# IR_LED_stick.net
KiCad netlist of a schematic drawn in EasyEDA
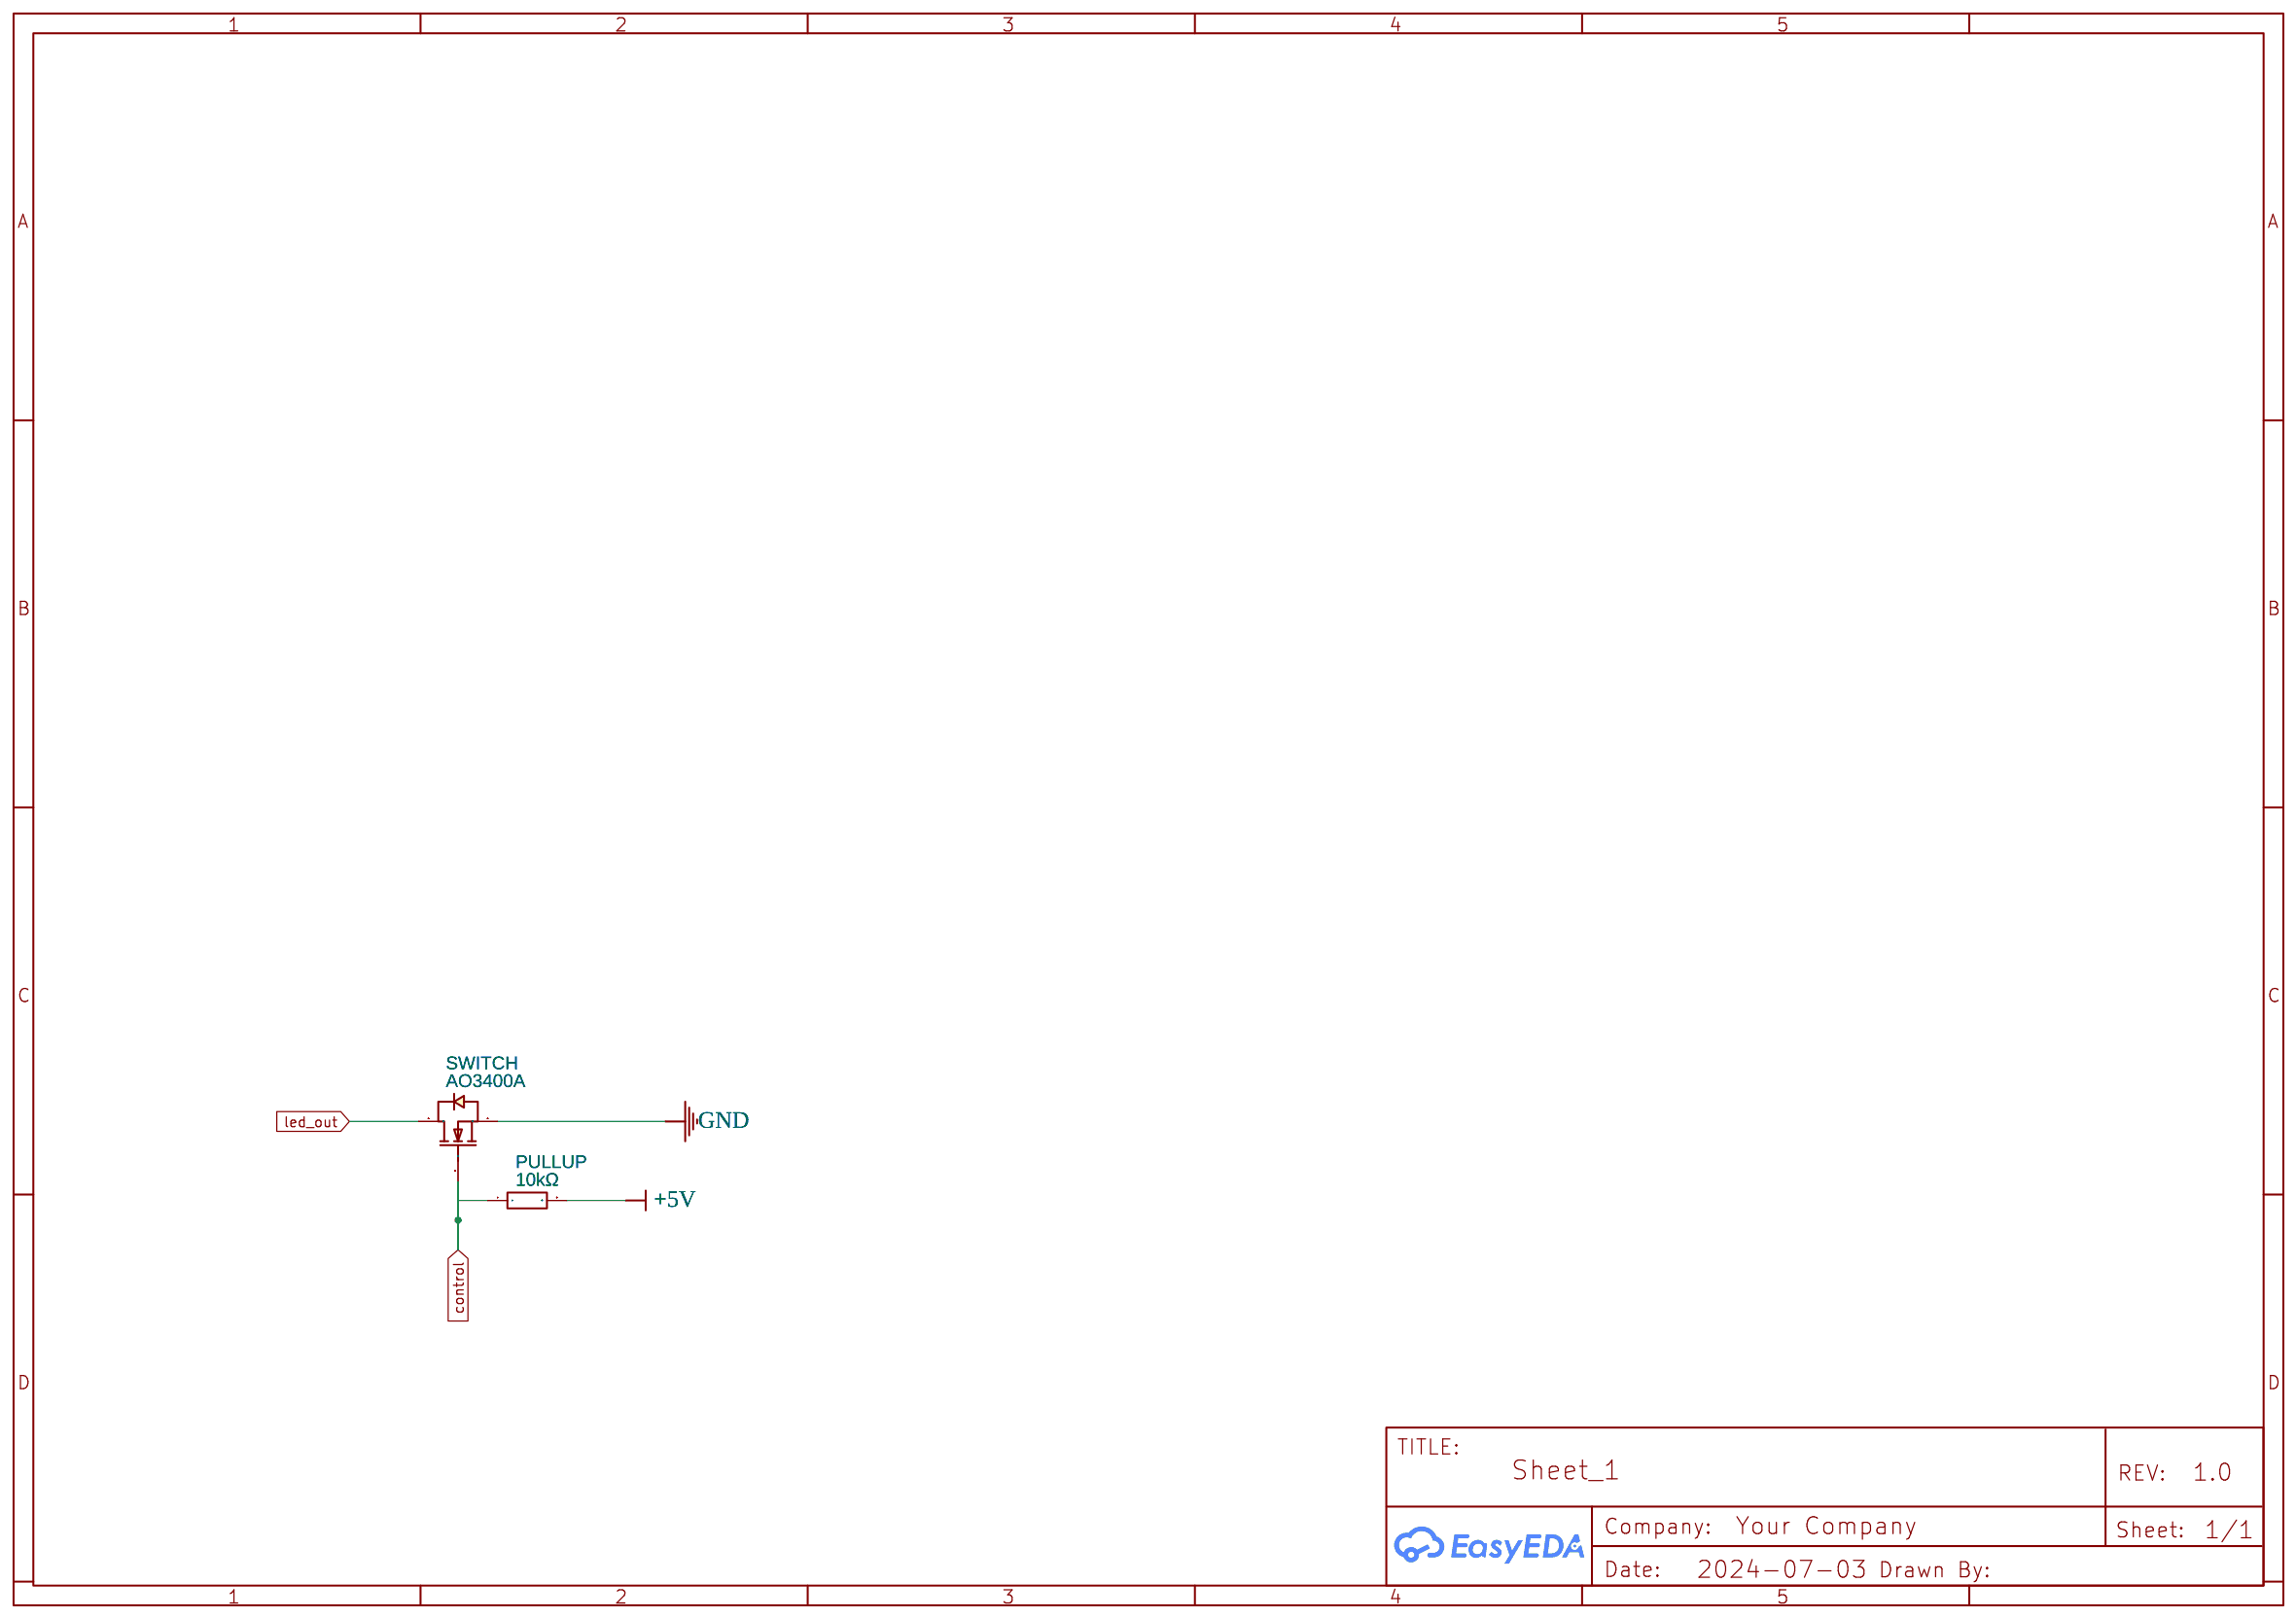
[diagram p0: Switch]
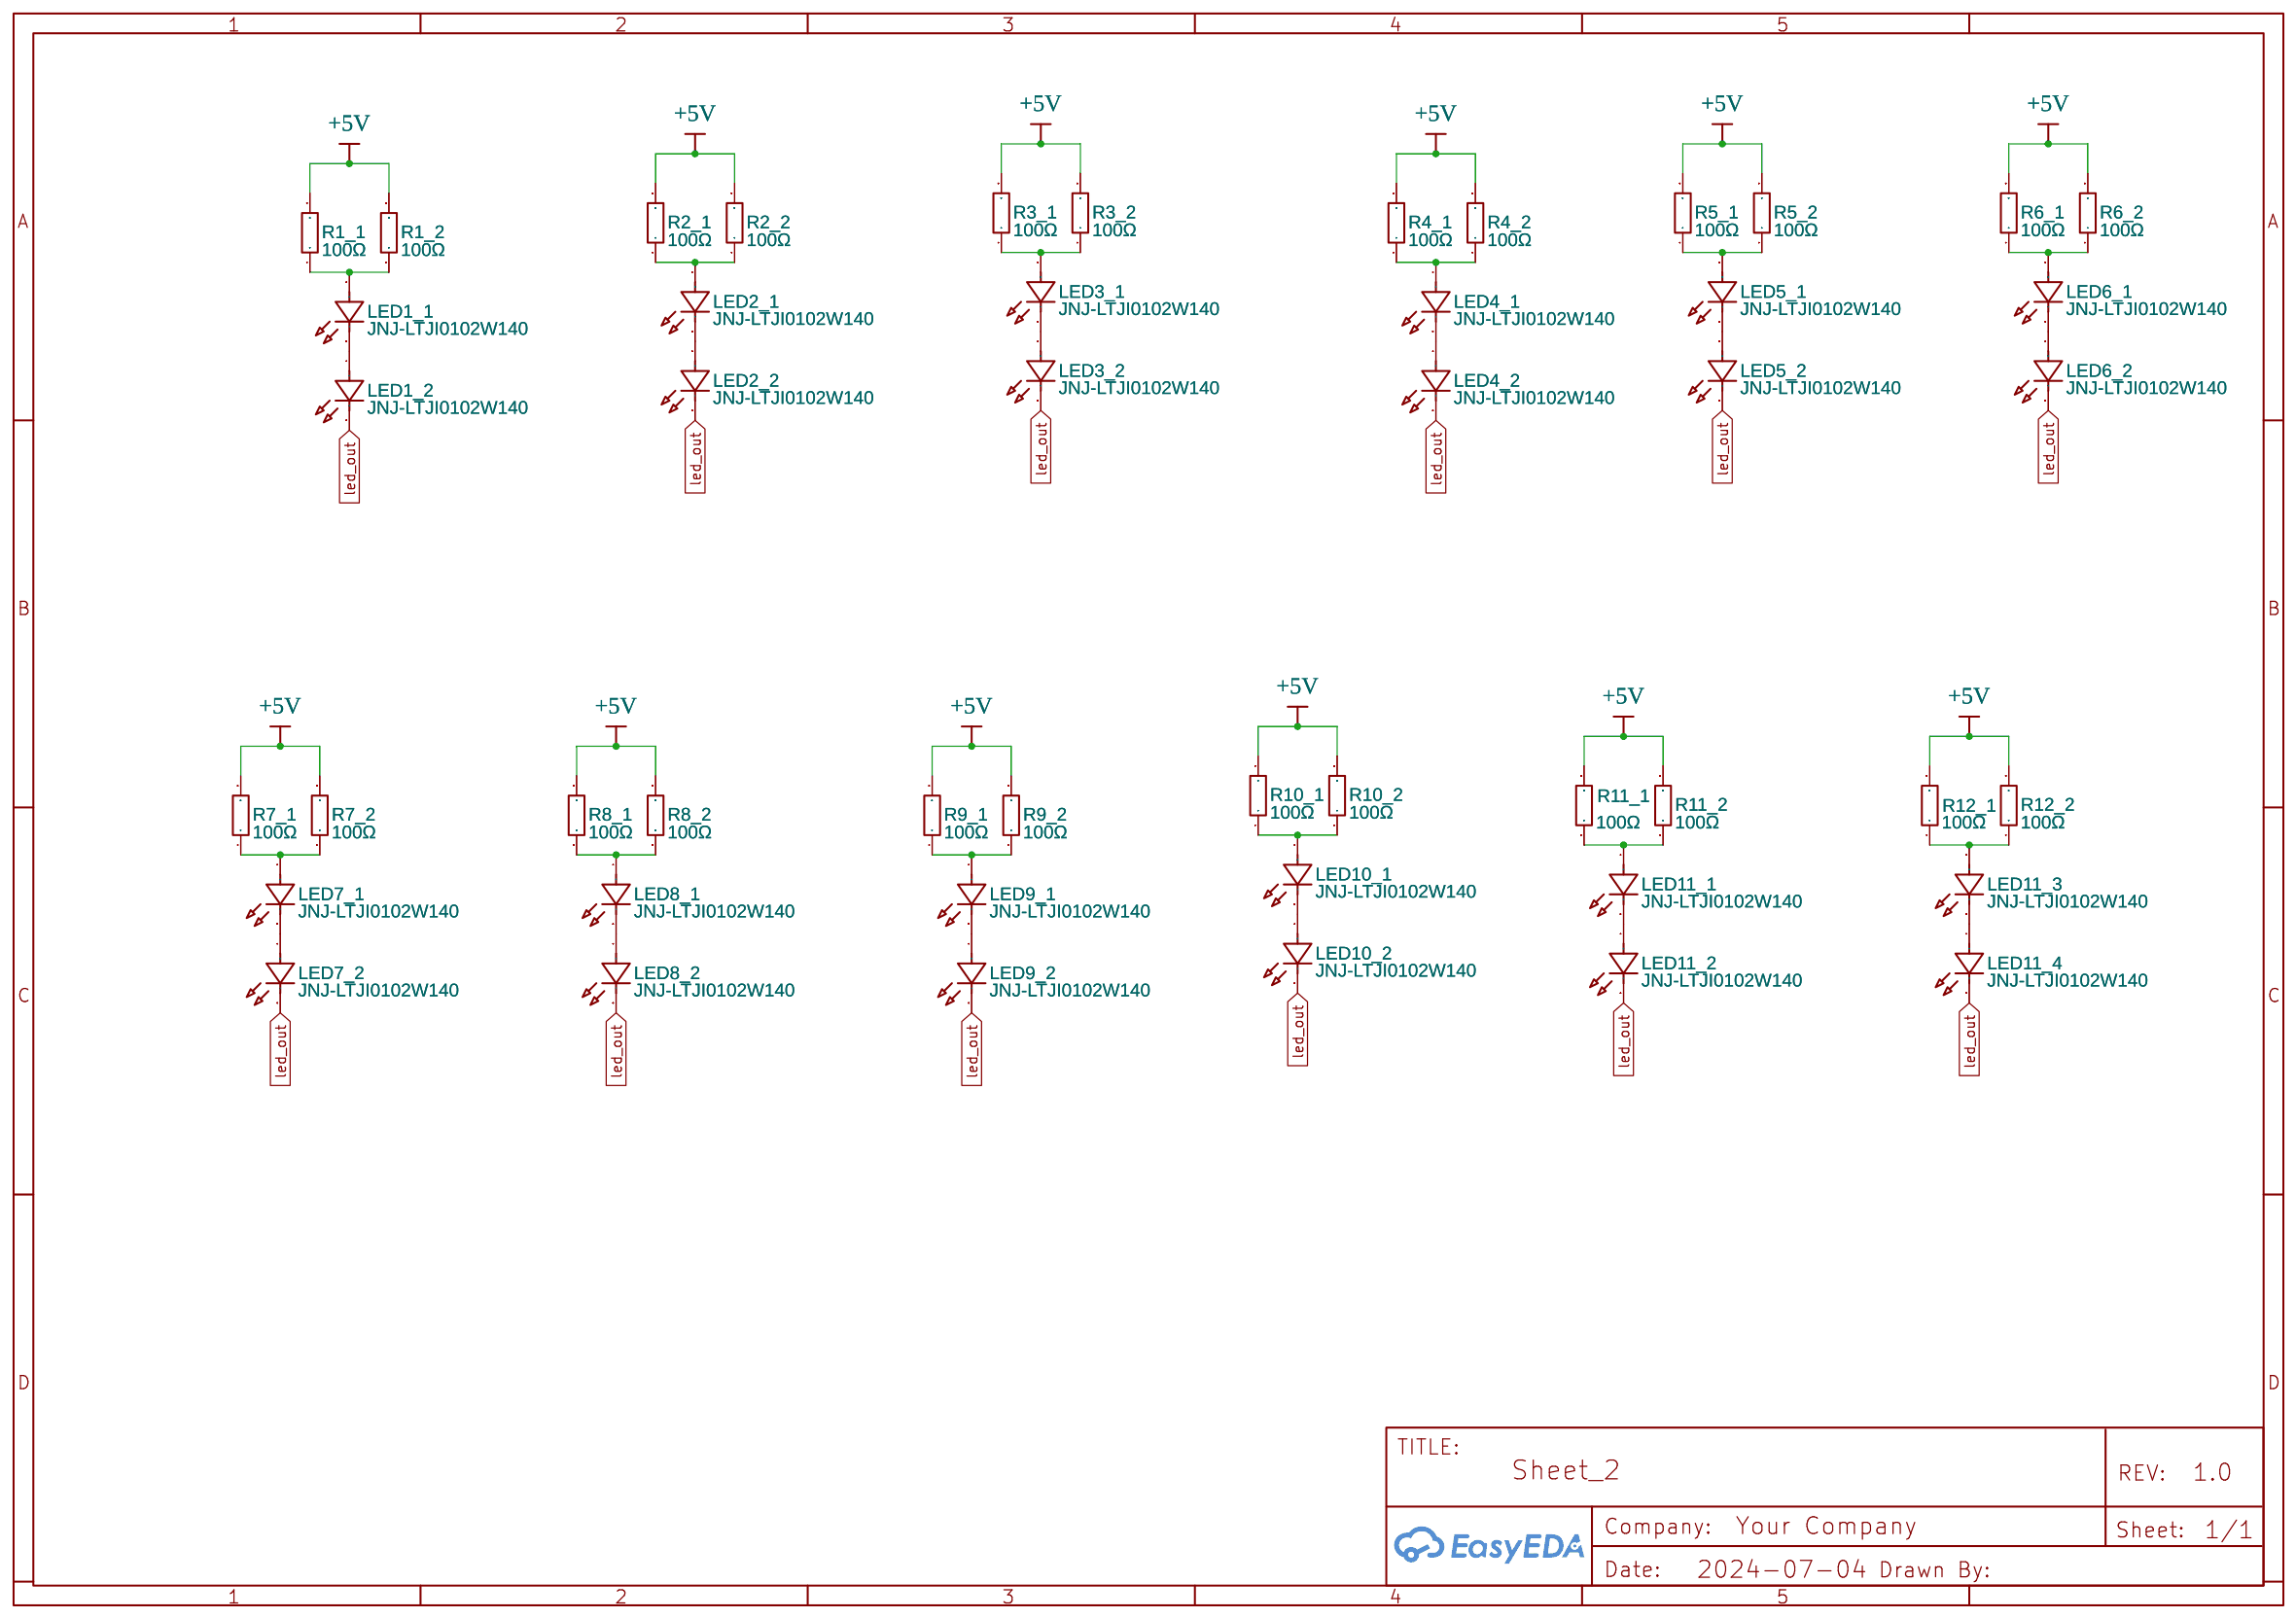
[diagram p1: LEDs]
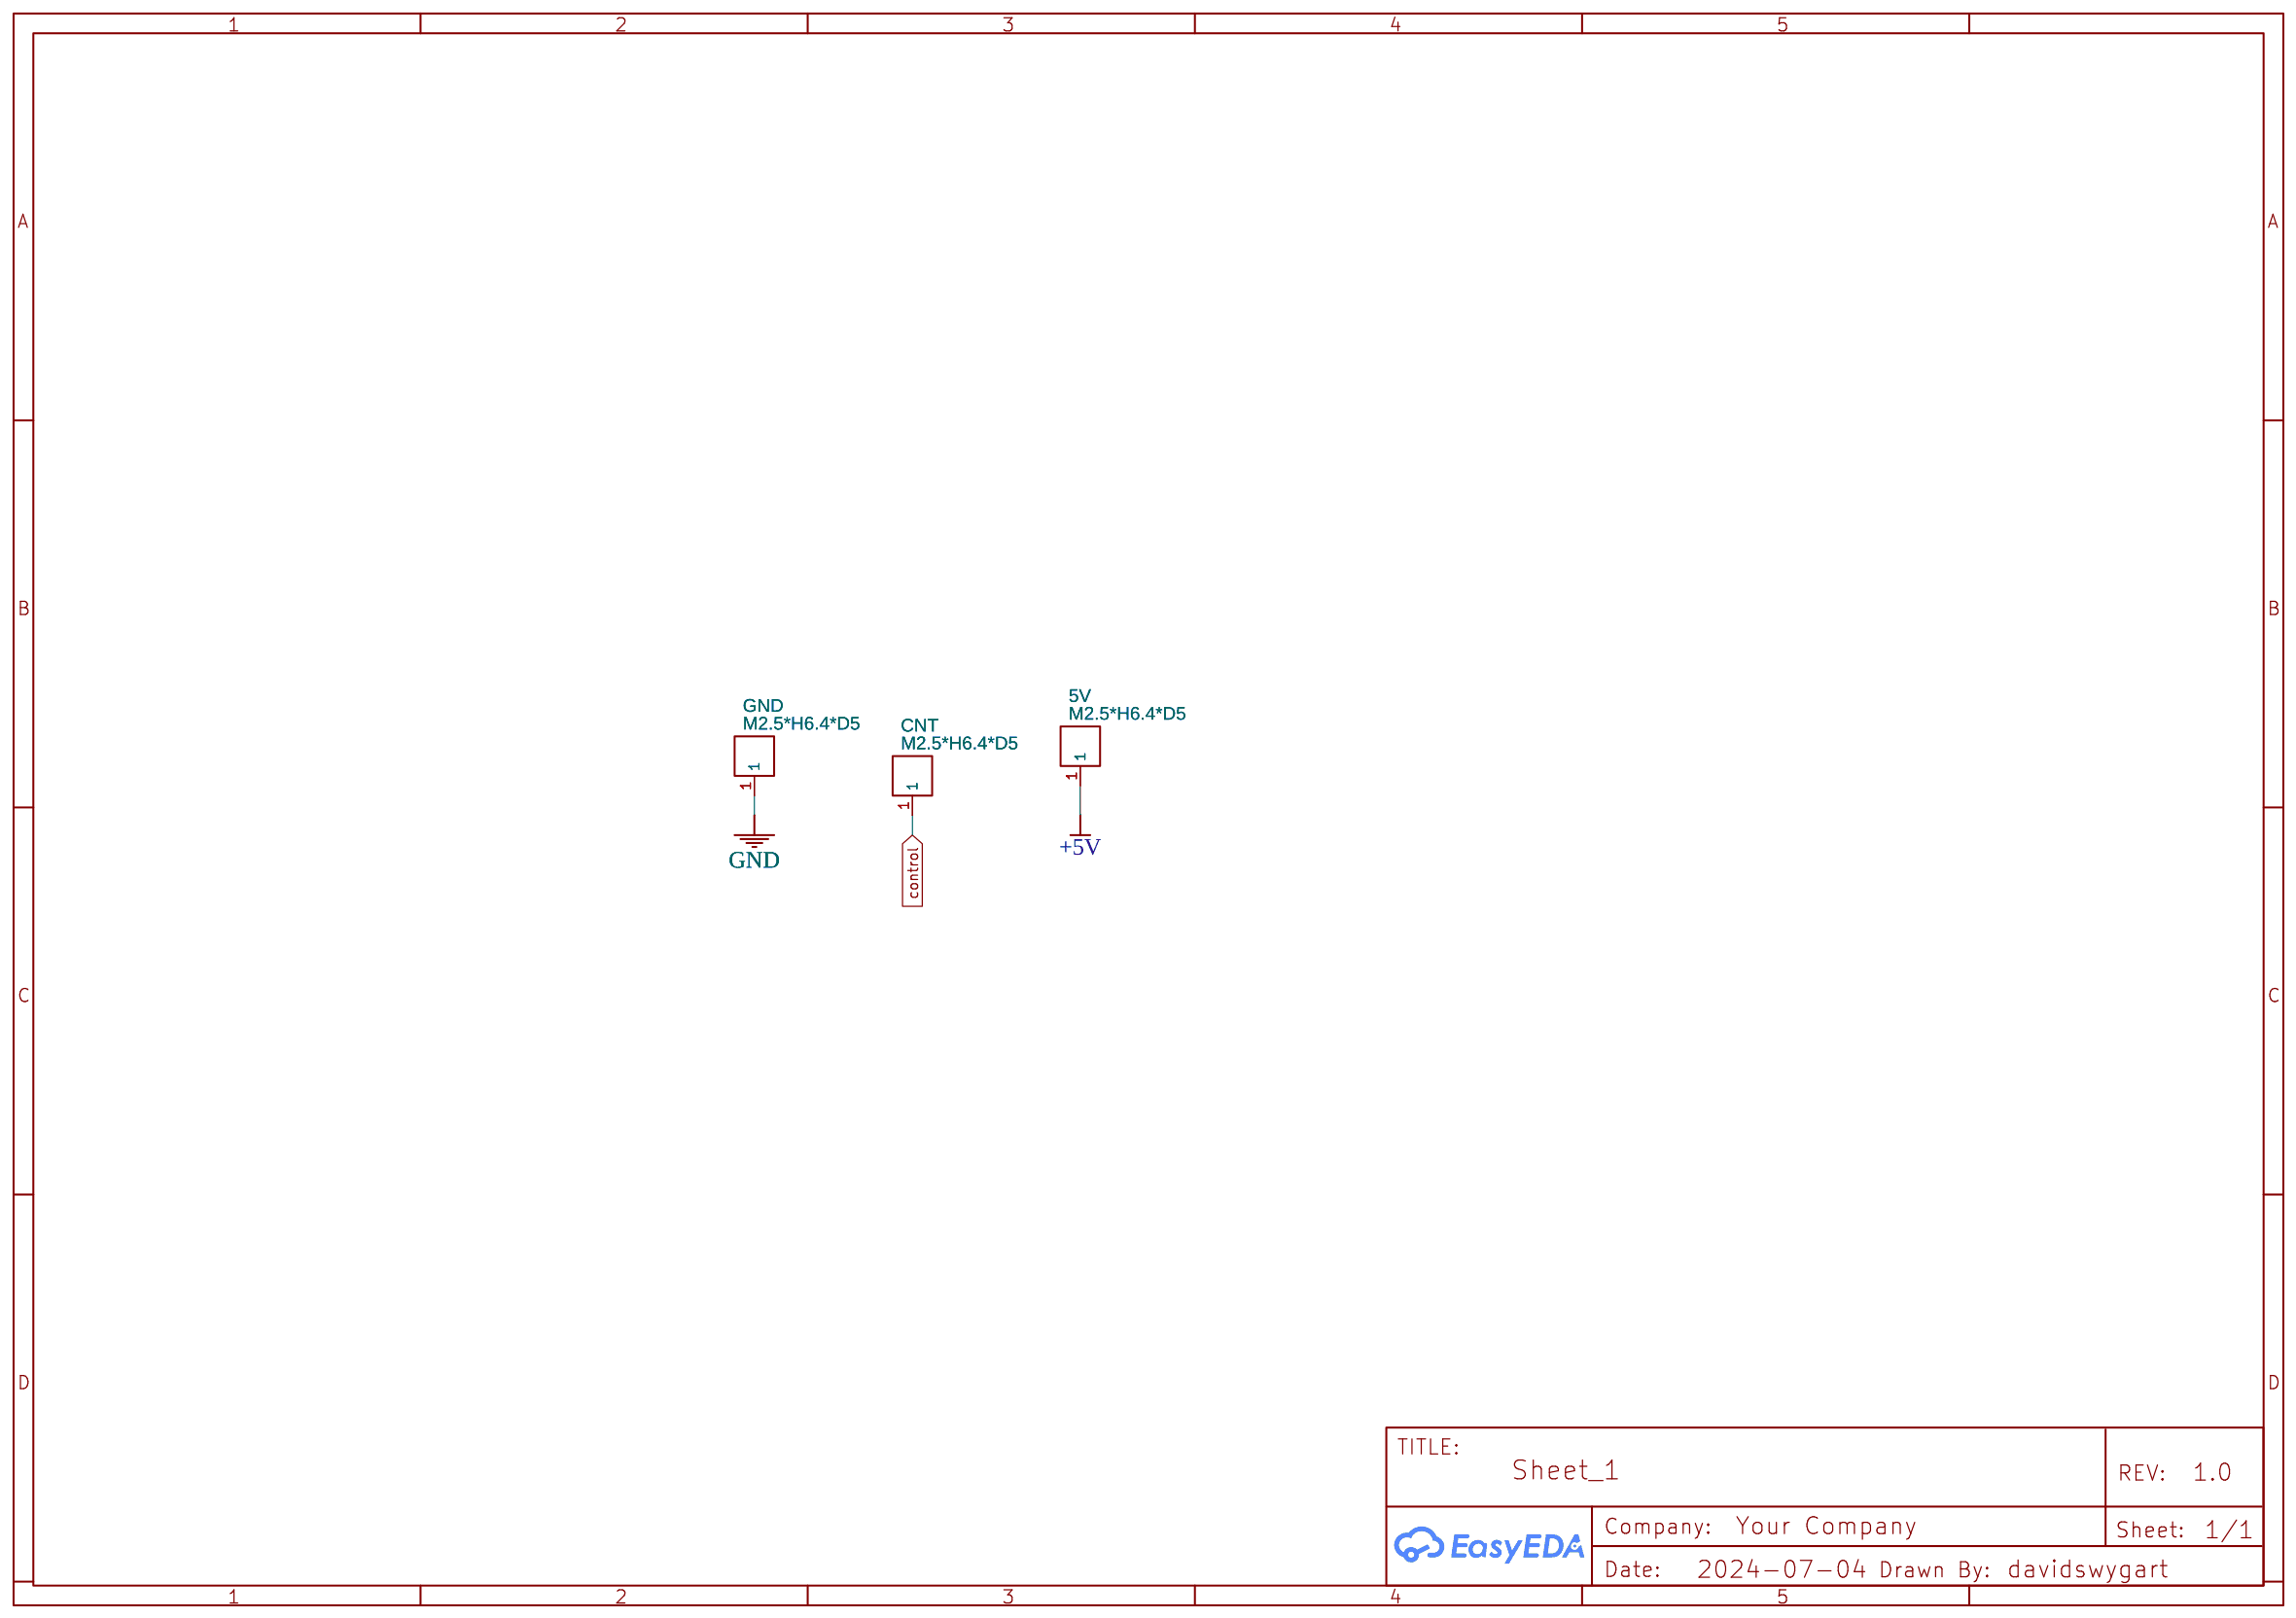
[diagram p2: IO]

(export (version "E")
  (design (tool "Eeschema 10.0.6"))
  (components
    (comp (ref "PULLUP")
      (value "10kΩ")
      (fields
        (field (name "Manufacturer Part") "0603WAF1002T5E")
        (field (name "Manufacturer") "UNI-ROYAL(厚声)")
      )
      (libsource (lib "") (part "0603WAF1002T5E"))
    )
    (comp (ref "SWITCH")
      (value "AO3400A")
      (fields (field (name "Manufacturer") "AOS"))
      (libsource (lib "") (part "AO3400A"))
    )
    (comp (ref "LED1_1")
      (value "JNJ-LTJI0102W140")
      (fields (field (name "Manufacturer") "JNJ OPTOELECTRONICS(强生光电)"))
      (libsource (lib "") (part "JNJ-LTJI0102W140_3"))
    )
    (comp (ref "LED1_2")
      (value "JNJ-LTJI0102W140")
      (fields (field (name "Manufacturer") "JNJ OPTOELECTRONICS(强生光电)"))
      (libsource (lib "") (part "JNJ-LTJI0102W140_3"))
    )
    (comp (ref "LED2_1")
      (value "JNJ-LTJI0102W140")
      (fields (field (name "Manufacturer") "JNJ OPTOELECTRONICS(强生光电)"))
      (libsource (lib "") (part "JNJ-LTJI0102W140"))
    )
    (comp (ref "LED2_2")
      (value "JNJ-LTJI0102W140")
      (fields (field (name "Manufacturer") "JNJ OPTOELECTRONICS(强生光电)"))
      (libsource (lib "") (part "JNJ-LTJI0102W140"))
    )
    (comp (ref "LED3_1")
      (value "JNJ-LTJI0102W140")
      (fields (field (name "Manufacturer") "JNJ OPTOELECTRONICS(强生光电)"))
      (libsource (lib "") (part "JNJ-LTJI0102W140_1"))
    )
    (comp (ref "LED3_2")
      (value "JNJ-LTJI0102W140")
      (fields (field (name "Manufacturer") "JNJ OPTOELECTRONICS(强生光电)"))
      (libsource (lib "") (part "JNJ-LTJI0102W140_1"))
    )
    (comp (ref "LED4_1")
      (value "JNJ-LTJI0102W140")
      (fields (field (name "Manufacturer") "JNJ OPTOELECTRONICS(强生光电)"))
      (libsource (lib "") (part "JNJ-LTJI0102W140_9"))
    )
    (comp (ref "LED4_2")
      (value "JNJ-LTJI0102W140")
      (fields (field (name "Manufacturer") "JNJ OPTOELECTRONICS(强生光电)"))
      (libsource (lib "") (part "JNJ-LTJI0102W140_9"))
    )
    (comp (ref "LED5_1")
      (value "JNJ-LTJI0102W140")
      (fields (field (name "Manufacturer") "JNJ OPTOELECTRONICS(强生光电)"))
      (libsource (lib "") (part "JNJ-LTJI0102W140_6"))
    )
    (comp (ref "LED5_2")
      (value "JNJ-LTJI0102W140")
      (fields (field (name "Manufacturer") "JNJ OPTOELECTRONICS(强生光电)"))
      (libsource (lib "") (part "JNJ-LTJI0102W140_6"))
    )
    (comp (ref "LED6_1")
      (value "JNJ-LTJI0102W140")
      (fields (field (name "Manufacturer") "JNJ OPTOELECTRONICS(强生光电)"))
      (libsource (lib "") (part "JNJ-LTJI0102W140_8"))
    )
    (comp (ref "LED6_2")
      (value "JNJ-LTJI0102W140")
      (fields (field (name "Manufacturer") "JNJ OPTOELECTRONICS(强生光电)"))
      (libsource (lib "") (part "JNJ-LTJI0102W140_8"))
    )
    (comp (ref "LED7_1")
      (value "JNJ-LTJI0102W140")
      (fields (field (name "Manufacturer") "JNJ OPTOELECTRONICS(强生光电)"))
      (libsource (lib "") (part "JNJ-LTJI0102W140_10"))
    )
    (comp (ref "LED7_2")
      (value "JNJ-LTJI0102W140")
      (fields (field (name "Manufacturer") "JNJ OPTOELECTRONICS(强生光电)"))
      (libsource (lib "") (part "JNJ-LTJI0102W140_10"))
    )
    (comp (ref "LED8_1")
      (value "JNJ-LTJI0102W140")
      (fields (field (name "Manufacturer") "JNJ OPTOELECTRONICS(强生光电)"))
      (libsource (lib "") (part "JNJ-LTJI0102W140_5"))
    )
    (comp (ref "LED8_2")
      (value "JNJ-LTJI0102W140")
      (fields (field (name "Manufacturer") "JNJ OPTOELECTRONICS(强生光电)"))
      (libsource (lib "") (part "JNJ-LTJI0102W140_5"))
    )
    (comp (ref "LED9_1")
      (value "JNJ-LTJI0102W140")
      (fields (field (name "Manufacturer") "JNJ OPTOELECTRONICS(强生光电)"))
      (libsource (lib "") (part "JNJ-LTJI0102W140_4"))
    )
    (comp (ref "LED9_2")
      (value "JNJ-LTJI0102W140")
      (fields (field (name "Manufacturer") "JNJ OPTOELECTRONICS(强生光电)"))
      (libsource (lib "") (part "JNJ-LTJI0102W140_4"))
    )
    (comp (ref "LED10_1")
      (value "JNJ-LTJI0102W140")
      (fields (field (name "Manufacturer") "JNJ OPTOELECTRONICS(强生光电)"))
      (libsource (lib "") (part "JNJ-LTJI0102W140_7"))
    )
    (comp (ref "LED10_2")
      (value "JNJ-LTJI0102W140")
      (fields (field (name "Manufacturer") "JNJ OPTOELECTRONICS(强生光电)"))
      (libsource (lib "") (part "JNJ-LTJI0102W140_7"))
    )
    (comp (ref "LED11_1")
      (value "JNJ-LTJI0102W140")
      (fields (field (name "Manufacturer") "JNJ OPTOELECTRONICS(强生光电)"))
      (libsource (lib "") (part "JNJ-LTJI0102W140_2"))
    )
    (comp (ref "LED11_2")
      (value "JNJ-LTJI0102W140")
      (fields (field (name "Manufacturer") "JNJ OPTOELECTRONICS(强生光电)"))
      (libsource (lib "") (part "JNJ-LTJI0102W140_2"))
    )
    (comp (ref "LED11_3")
      (value "JNJ-LTJI0102W140")
      (fields (field (name "Manufacturer") "JNJ OPTOELECTRONICS(强生光电)"))
      (libsource (lib "") (part "JNJ-LTJI0102W140_2"))
    )
    (comp (ref "LED11_4")
      (value "JNJ-LTJI0102W140")
      (fields (field (name "Manufacturer") "JNJ OPTOELECTRONICS(强生光电)"))
      (libsource (lib "") (part "JNJ-LTJI0102W140_2"))
    )
    (comp (ref "R1_1")
      (value "100Ω")
      (fields
        (field (name "Manufacturer Part") "0805W8F1000T5E")
        (field (name "Manufacturer") "UNI-ROYAL(厚声)")
      )
      (libsource (lib "") (part "0805W8F1000T5E_6"))
    )
    (comp (ref "R1_2")
      (value "100Ω")
      (fields
        (field (name "Manufacturer Part") "0805W8F1000T5E")
        (field (name "Manufacturer") "UNI-ROYAL(厚声)")
      )
      (libsource (lib "") (part "0805W8F1000T5E_6"))
    )
    (comp (ref "R2_1")
      (value "100Ω")
      (fields
        (field (name "Manufacturer Part") "0805W8F1000T5E")
        (field (name "Manufacturer") "UNI-ROYAL(厚声)")
      )
      (libsource (lib "") (part "0805W8F1000T5E_10"))
    )
    (comp (ref "R2_2")
      (value "100Ω")
      (fields
        (field (name "Manufacturer Part") "0805W8F1000T5E")
        (field (name "Manufacturer") "UNI-ROYAL(厚声)")
      )
      (libsource (lib "") (part "0805W8F1000T5E_10"))
    )
    (comp (ref "R3_1")
      (value "100Ω")
      (fields
        (field (name "Manufacturer Part") "0805W8F1000T5E")
        (field (name "Manufacturer") "UNI-ROYAL(厚声)")
      )
      (libsource (lib "") (part "0805W8F1000T5E_2"))
    )
    (comp (ref "R3_2")
      (value "100Ω")
      (fields
        (field (name "Manufacturer Part") "0805W8F1000T5E")
        (field (name "Manufacturer") "UNI-ROYAL(厚声)")
      )
      (libsource (lib "") (part "0805W8F1000T5E_2"))
    )
    (comp (ref "R4_1")
      (value "100Ω")
      (fields
        (field (name "Manufacturer Part") "0805W8F1000T5E")
        (field (name "Manufacturer") "UNI-ROYAL(厚声)")
      )
      (libsource (lib "") (part "0805W8F1000T5E_5"))
    )
    (comp (ref "R4_2")
      (value "100Ω")
      (fields
        (field (name "Manufacturer Part") "0805W8F1000T5E")
        (field (name "Manufacturer") "UNI-ROYAL(厚声)")
      )
      (libsource (lib "") (part "0805W8F1000T5E_5"))
    )
    (comp (ref "R5_1")
      (value "100Ω")
      (fields
        (field (name "Manufacturer Part") "0805W8F1000T5E")
        (field (name "Manufacturer") "UNI-ROYAL(厚声)")
      )
      (libsource (lib "") (part "0805W8F1000T5E_8"))
    )
    (comp (ref "R5_2")
      (value "100Ω")
      (fields
        (field (name "Manufacturer Part") "0805W8F1000T5E")
        (field (name "Manufacturer") "UNI-ROYAL(厚声)")
      )
      (libsource (lib "") (part "0805W8F1000T5E_8"))
    )
    (comp (ref "R6_1")
      (value "100Ω")
      (fields
        (field (name "Manufacturer Part") "0805W8F1000T5E")
        (field (name "Manufacturer") "UNI-ROYAL(厚声)")
      )
      (libsource (lib "") (part "0805W8F1000T5E_4"))
    )
    (comp (ref "R6_2")
      (value "100Ω")
      (fields
        (field (name "Manufacturer Part") "0805W8F1000T5E")
        (field (name "Manufacturer") "UNI-ROYAL(厚声)")
      )
      (libsource (lib "") (part "0805W8F1000T5E_4"))
    )
    (comp (ref "R7_1")
      (value "100Ω")
      (fields
        (field (name "Manufacturer Part") "0805W8F1000T5E")
        (field (name "Manufacturer") "UNI-ROYAL(厚声)")
      )
      (libsource (lib "") (part "0805W8F1000T5E_1"))
    )
    (comp (ref "R7_2")
      (value "100Ω")
      (fields
        (field (name "Manufacturer Part") "0805W8F1000T5E")
        (field (name "Manufacturer") "UNI-ROYAL(厚声)")
      )
      (libsource (lib "") (part "0805W8F1000T5E_1"))
    )
    (comp (ref "R8_1")
      (value "100Ω")
      (fields
        (field (name "Manufacturer Part") "0805W8F1000T5E")
        (field (name "Manufacturer") "UNI-ROYAL(厚声)")
      )
      (libsource (lib "") (part "0805W8F1000T5E"))
    )
    (comp (ref "R8_2")
      (value "100Ω")
      (fields
        (field (name "Manufacturer Part") "0805W8F1000T5E")
        (field (name "Manufacturer") "UNI-ROYAL(厚声)")
      )
      (libsource (lib "") (part "0805W8F1000T5E"))
    )
    (comp (ref "R9_1")
      (value "100Ω")
      (fields
        (field (name "Manufacturer Part") "0805W8F1000T5E")
        (field (name "Manufacturer") "UNI-ROYAL(厚声)")
      )
      (libsource (lib "") (part "0805W8F1000T5E_7"))
    )
    (comp (ref "R9_2")
      (value "100Ω")
      (fields
        (field (name "Manufacturer Part") "0805W8F1000T5E")
        (field (name "Manufacturer") "UNI-ROYAL(厚声)")
      )
      (libsource (lib "") (part "0805W8F1000T5E_7"))
    )
    (comp (ref "R10_1")
      (value "100Ω")
      (fields
        (field (name "Manufacturer Part") "0805W8F1000T5E")
        (field (name "Manufacturer") "UNI-ROYAL(厚声)")
      )
      (libsource (lib "") (part "0805W8F1000T5E_11"))
    )
    (comp (ref "R10_2")
      (value "100Ω")
      (fields
        (field (name "Manufacturer Part") "0805W8F1000T5E")
        (field (name "Manufacturer") "UNI-ROYAL(厚声)")
      )
      (libsource (lib "") (part "0805W8F1000T5E_11"))
    )
    (comp (ref "R11_1")
      (value "100Ω")
      (fields
        (field (name "Manufacturer Part") "0805W8F1000T5E")
        (field (name "Manufacturer") "UNI-ROYAL(厚声)")
      )
      (libsource (lib "") (part "0805W8F1000T5E_3"))
    )
    (comp (ref "R11_2")
      (value "100Ω")
      (fields
        (field (name "Manufacturer Part") "0805W8F1000T5E")
        (field (name "Manufacturer") "UNI-ROYAL(厚声)")
      )
      (libsource (lib "") (part "0805W8F1000T5E_3"))
    )
    (comp (ref "R12_1")
      (value "100Ω")
      (fields
        (field (name "Manufacturer Part") "0805W8F1000T5E")
        (field (name "Manufacturer") "UNI-ROYAL(厚声)")
      )
      (libsource (lib "") (part "0805W8F1000T5E_9"))
    )
    (comp (ref "R12_2")
      (value "100Ω")
      (fields
        (field (name "Manufacturer Part") "0805W8F1000T5E")
        (field (name "Manufacturer") "UNI-ROYAL(厚声)")
      )
      (libsource (lib "") (part "0805W8F1000T5E_9"))
    )
    (comp (ref "5V") (value "M2.5*H6.4*D5") (libsource (lib "") (part "M2.5*H6.4*D5_1")))
    (comp (ref "CNT") (value "M2.5*H6.4*D5") (libsource (lib "") (part "M2.5*H6.4*D5")))
    (comp (ref "GND") (value "M2.5*H6.4*D5") (libsource (lib "") (part "M2.5*H6.4*D5_2")))
  )
  (nets
    (net (code "1") (name "+5V") (class "Default")
      (node (ref "5V") (pin "1") (pinfunction "1_1") (pintype "unspecified"))
      (node (ref "PULLUP") (pin "2") (pinfunction "2_2") (pintype "input"))
      (node (ref "R10_1") (pin "2") (pinfunction "2_2") (pintype "input"))
      (node (ref "R10_2") (pin "2") (pinfunction "2_2") (pintype "input"))
      (node (ref "R11_1") (pin "2") (pinfunction "2_2") (pintype "input"))
      (node (ref "R11_2") (pin "2") (pinfunction "2_2") (pintype "input"))
      (node (ref "R12_1") (pin "2") (pinfunction "2_2") (pintype "input"))
      (node (ref "R12_2") (pin "2") (pinfunction "2_2") (pintype "input"))
      (node (ref "R1_1") (pin "2") (pinfunction "2_2") (pintype "input"))
      (node (ref "R1_2") (pin "2") (pinfunction "2_2") (pintype "input"))
      (node (ref "R2_1") (pin "2") (pinfunction "2_2") (pintype "input"))
      (node (ref "R2_2") (pin "2") (pinfunction "2_2") (pintype "input"))
      (node (ref "R3_1") (pin "2") (pinfunction "2_2") (pintype "input"))
      (node (ref "R3_2") (pin "2") (pinfunction "2_2") (pintype "input"))
      (node (ref "R4_1") (pin "2") (pinfunction "2_2") (pintype "input"))
      (node (ref "R4_2") (pin "2") (pinfunction "2_2") (pintype "input"))
      (node (ref "R5_1") (pin "2") (pinfunction "2_2") (pintype "input"))
      (node (ref "R5_2") (pin "2") (pinfunction "2_2") (pintype "input"))
      (node (ref "R6_1") (pin "2") (pinfunction "2_2") (pintype "input"))
      (node (ref "R6_2") (pin "2") (pinfunction "2_2") (pintype "input"))
      (node (ref "R7_1") (pin "2") (pinfunction "2_2") (pintype "input"))
      (node (ref "R7_2") (pin "2") (pinfunction "2_2") (pintype "input"))
      (node (ref "R8_1") (pin "2") (pinfunction "2_2") (pintype "input"))
      (node (ref "R8_2") (pin "2") (pinfunction "2_2") (pintype "input"))
      (node (ref "R9_1") (pin "2") (pinfunction "2_2") (pintype "input"))
      (node (ref "R9_2") (pin "2") (pinfunction "2_2") (pintype "input"))
    )
    (net (code "2") (name "GND") (class "Default")
      (node (ref "GND") (pin "1") (pinfunction "1_1") (pintype "unspecified"))
      (node (ref "SWITCH") (pin "2") (pinfunction "S_2") (pintype "unspecified"))
    )
    (net (code "3") (name "Net-(LED1_1-+)") (class "Default")
      (node (ref "LED1_1") (pin "1") (pinfunction "+_1") (pintype "unspecified"))
      (node (ref "R1_1") (pin "1") (pinfunction "1_1") (pintype "input"))
      (node (ref "R1_2") (pin "1") (pinfunction "1_1") (pintype "input"))
    )
    (net (code "4") (name "Net-(LED1_1--)") (class "Default")
      (node (ref "LED1_1") (pin "2") (pinfunction "-_2") (pintype "unspecified"))
      (node (ref "LED1_2") (pin "1") (pinfunction "+_1") (pintype "unspecified"))
    )
    (net (code "5") (name "Net-(LED2_1-+)") (class "Default")
      (node (ref "LED2_1") (pin "1") (pinfunction "+_1") (pintype "unspecified"))
      (node (ref "R2_1") (pin "1") (pinfunction "1_1") (pintype "input"))
      (node (ref "R2_2") (pin "1") (pinfunction "1_1") (pintype "input"))
    )
    (net (code "6") (name "Net-(LED2_1--)") (class "Default")
      (node (ref "LED2_1") (pin "2") (pinfunction "-_2") (pintype "unspecified"))
      (node (ref "LED2_2") (pin "1") (pinfunction "+_1") (pintype "unspecified"))
    )
    (net (code "7") (name "Net-(LED3_1-+)") (class "Default")
      (node (ref "LED3_1") (pin "1") (pinfunction "+_1") (pintype "unspecified"))
      (node (ref "R3_1") (pin "1") (pinfunction "1_1") (pintype "input"))
      (node (ref "R3_2") (pin "1") (pinfunction "1_1") (pintype "input"))
    )
    (net (code "8") (name "Net-(LED3_1--)") (class "Default")
      (node (ref "LED3_1") (pin "2") (pinfunction "-_2") (pintype "unspecified"))
      (node (ref "LED3_2") (pin "1") (pinfunction "+_1") (pintype "unspecified"))
    )
    (net (code "9") (name "Net-(LED4_1-+)") (class "Default")
      (node (ref "LED4_1") (pin "1") (pinfunction "+_1") (pintype "unspecified"))
      (node (ref "R4_1") (pin "1") (pinfunction "1_1") (pintype "input"))
      (node (ref "R4_2") (pin "1") (pinfunction "1_1") (pintype "input"))
    )
    (net (code "10") (name "Net-(LED4_1--)") (class "Default")
      (node (ref "LED4_1") (pin "2") (pinfunction "-_2") (pintype "unspecified"))
      (node (ref "LED4_2") (pin "1") (pinfunction "+_1") (pintype "unspecified"))
    )
    (net (code "11") (name "Net-(LED5_1-+)") (class "Default")
      (node (ref "LED5_1") (pin "1") (pinfunction "+_1") (pintype "unspecified"))
      (node (ref "R5_1") (pin "1") (pinfunction "1_1") (pintype "input"))
      (node (ref "R5_2") (pin "1") (pinfunction "1_1") (pintype "input"))
    )
    (net (code "12") (name "Net-(LED5_1--)") (class "Default")
      (node (ref "LED5_1") (pin "2") (pinfunction "-_2") (pintype "unspecified"))
      (node (ref "LED5_2") (pin "1") (pinfunction "+_1") (pintype "unspecified"))
    )
    (net (code "13") (name "Net-(LED6_1-+)") (class "Default")
      (node (ref "LED6_1") (pin "1") (pinfunction "+_1") (pintype "unspecified"))
      (node (ref "R6_1") (pin "1") (pinfunction "1_1") (pintype "input"))
      (node (ref "R6_2") (pin "1") (pinfunction "1_1") (pintype "input"))
    )
    (net (code "14") (name "Net-(LED6_1--)") (class "Default")
      (node (ref "LED6_1") (pin "2") (pinfunction "-_2") (pintype "unspecified"))
      (node (ref "LED6_2") (pin "1") (pinfunction "+_1") (pintype "unspecified"))
    )
    (net (code "15") (name "Net-(LED7_1-+)") (class "Default")
      (node (ref "LED7_1") (pin "1") (pinfunction "+_1") (pintype "unspecified"))
      (node (ref "R7_1") (pin "1") (pinfunction "1_1") (pintype "input"))
      (node (ref "R7_2") (pin "1") (pinfunction "1_1") (pintype "input"))
    )
    (net (code "16") (name "Net-(LED7_1--)") (class "Default")
      (node (ref "LED7_1") (pin "2") (pinfunction "-_2") (pintype "unspecified"))
      (node (ref "LED7_2") (pin "1") (pinfunction "+_1") (pintype "unspecified"))
    )
    (net (code "17") (name "Net-(LED8_1-+)") (class "Default")
      (node (ref "LED8_1") (pin "1") (pinfunction "+_1") (pintype "unspecified"))
      (node (ref "R8_1") (pin "1") (pinfunction "1_1") (pintype "input"))
      (node (ref "R8_2") (pin "1") (pinfunction "1_1") (pintype "input"))
    )
    (net (code "18") (name "Net-(LED8_1--)") (class "Default")
      (node (ref "LED8_1") (pin "2") (pinfunction "-_2") (pintype "unspecified"))
      (node (ref "LED8_2") (pin "1") (pinfunction "+_1") (pintype "unspecified"))
    )
    (net (code "19") (name "Net-(LED9_1-+)") (class "Default")
      (node (ref "LED9_1") (pin "1") (pinfunction "+_1") (pintype "unspecified"))
      (node (ref "R9_1") (pin "1") (pinfunction "1_1") (pintype "input"))
      (node (ref "R9_2") (pin "1") (pinfunction "1_1") (pintype "input"))
    )
    (net (code "20") (name "Net-(LED9_1--)") (class "Default")
      (node (ref "LED9_1") (pin "2") (pinfunction "-_2") (pintype "unspecified"))
      (node (ref "LED9_2") (pin "1") (pinfunction "+_1") (pintype "unspecified"))
    )
    (net (code "21") (name "Net-(LED10_1-+)") (class "Default")
      (node (ref "LED10_1") (pin "1") (pinfunction "+_1") (pintype "unspecified"))
      (node (ref "R10_1") (pin "1") (pinfunction "1_1") (pintype "input"))
      (node (ref "R10_2") (pin "1") (pinfunction "1_1") (pintype "input"))
    )
    (net (code "22") (name "Net-(LED10_1--)") (class "Default")
      (node (ref "LED10_1") (pin "2") (pinfunction "-_2") (pintype "unspecified"))
      (node (ref "LED10_2") (pin "1") (pinfunction "+_1") (pintype "unspecified"))
    )
    (net (code "23") (name "Net-(LED11_1-+)") (class "Default")
      (node (ref "LED11_1") (pin "1") (pinfunction "+_1") (pintype "unspecified"))
      (node (ref "R11_1") (pin "1") (pinfunction "1_1") (pintype "input"))
      (node (ref "R11_2") (pin "1") (pinfunction "1_1") (pintype "input"))
    )
    (net (code "24") (name "Net-(LED11_1--)") (class "Default")
      (node (ref "LED11_1") (pin "2") (pinfunction "-_2") (pintype "unspecified"))
      (node (ref "LED11_2") (pin "1") (pinfunction "+_1") (pintype "unspecified"))
    )
    (net (code "25") (name "Net-(LED11_3-+)") (class "Default")
      (node (ref "LED11_3") (pin "1") (pinfunction "+_1") (pintype "unspecified"))
      (node (ref "R12_1") (pin "1") (pinfunction "1_1") (pintype "input"))
      (node (ref "R12_2") (pin "1") (pinfunction "1_1") (pintype "input"))
    )
    (net (code "26") (name "Net-(LED11_3--)") (class "Default")
      (node (ref "LED11_3") (pin "2") (pinfunction "-_2") (pintype "unspecified"))
      (node (ref "LED11_4") (pin "1") (pinfunction "+_1") (pintype "unspecified"))
    )
    (net (code "27") (name "control") (class "Default")
      (node (ref "CNT") (pin "1") (pinfunction "1_1") (pintype "unspecified"))
      (node (ref "PULLUP") (pin "1") (pinfunction "1_1") (pintype "input"))
      (node (ref "SWITCH") (pin "1") (pinfunction "G_1") (pintype "unspecified"))
    )
    (net (code "28") (name "led_out") (class "Default")
      (node (ref "LED10_2") (pin "2") (pinfunction "-_2") (pintype "unspecified"))
      (node (ref "LED11_2") (pin "2") (pinfunction "-_2") (pintype "unspecified"))
      (node (ref "LED11_4") (pin "2") (pinfunction "-_2") (pintype "unspecified"))
      (node (ref "LED1_2") (pin "2") (pinfunction "-_2") (pintype "unspecified"))
      (node (ref "LED2_2") (pin "2") (pinfunction "-_2") (pintype "unspecified"))
      (node (ref "LED3_2") (pin "2") (pinfunction "-_2") (pintype "unspecified"))
      (node (ref "LED4_2") (pin "2") (pinfunction "-_2") (pintype "unspecified"))
      (node (ref "LED5_2") (pin "2") (pinfunction "-_2") (pintype "unspecified"))
      (node (ref "LED6_2") (pin "2") (pinfunction "-_2") (pintype "unspecified"))
      (node (ref "LED7_2") (pin "2") (pinfunction "-_2") (pintype "unspecified"))
      (node (ref "LED8_2") (pin "2") (pinfunction "-_2") (pintype "unspecified"))
      (node (ref "LED9_2") (pin "2") (pinfunction "-_2") (pintype "unspecified"))
      (node (ref "SWITCH") (pin "3") (pinfunction "D_3") (pintype "unspecified"))
    )
  )
)
